# AD9361_EXT.net
KiCad netlist of a schematic drawn in Altium Designer
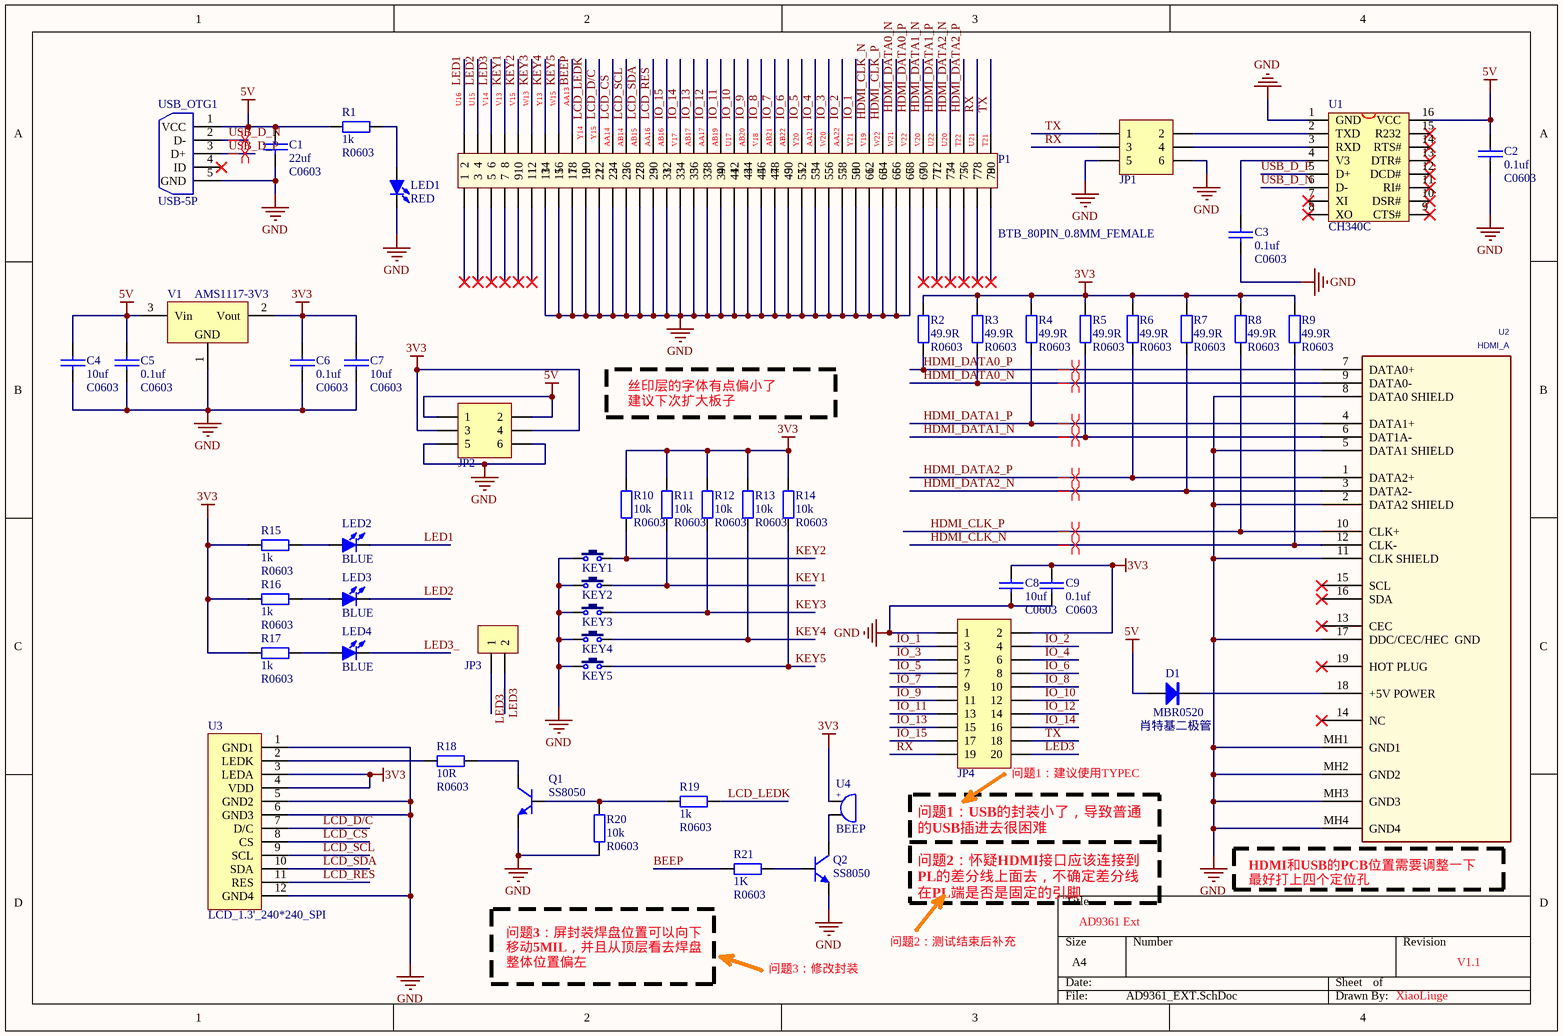
[diagram p0: AD9361_EXT.SchDoc]

(export (version "E")
  (design (tool "Eeschema 10.0.6"))
  (components
    (comp (ref "C1")
      (value "22uf")
      (footprint "C0603")
      (description "0603无极性贴片电容")
      (libsource (lib "电容") (part "CAP_0603"))
    )
    (comp (ref "C2")
      (value "0.1uf")
      (footprint "C0603")
      (description "0603无极性贴片电容")
      (libsource (lib "电容") (part "CAP_0603"))
    )
    (comp (ref "C3")
      (value "0.1uf")
      (footprint "C0603")
      (description "0603无极性贴片电容")
      (libsource (lib "电容") (part "CAP_0603"))
    )
    (comp (ref "C4")
      (value "10uf")
      (footprint "C0603")
      (description "0603无极性贴片电容")
      (libsource (lib "电容") (part "CAP_0603"))
    )
    (comp (ref "C5")
      (value "0.1uf")
      (footprint "C0603")
      (description "0603无极性贴片电容")
      (libsource (lib "电容") (part "CAP_0603"))
    )
    (comp (ref "C6")
      (value "0.1uf")
      (footprint "C0603")
      (description "0603无极性贴片电容")
      (libsource (lib "电容") (part "CAP_0603"))
    )
    (comp (ref "C7")
      (value "10uf")
      (footprint "C0603")
      (description "0603无极性贴片电容")
      (libsource (lib "电容") (part "CAP_0603"))
    )
    (comp (ref "C8")
      (value "10uf")
      (footprint "C0603")
      (description "0603无极性贴片电容")
      (libsource (lib "电容") (part "CAP_0603"))
    )
    (comp (ref "C9")
      (value "0.1uf")
      (footprint "C0603")
      (description "0603无极性贴片电容")
      (libsource (lib "电容") (part "CAP_0603"))
    )
    (comp (ref "D1")
      (value "MBR0520")
      (footprint "SOD-323")
      (description "肖特基二极管")
      (fields (field (name "BOM蜜称") "肖特基二极管"))
      (libsource (lib "二极管") (part "SS14"))
    )
    (comp (ref "JP1")
      (value "Header3X2")
      (footprint "HDR2.54-LI-2x3P")
      (description "3*2P接插件")
      (libsource (lib "排针") (part "Header 3X2"))
    )
    (comp (ref "JP2")
      (value "Header3X2")
      (footprint "HDR2.54-LI-2x3P")
      (description "3*2P接插件")
      (libsource (lib "排针") (part "Header 3X2"))
    )
    (comp (ref "JP3")
      (value "HDR-1X2")
      (footprint "HDR2.54-LI-2P")
      (description "2P接插件")
      (libsource (lib "排针") (part "Header 2"))
    )
    (comp (ref "JP4")
      (value "Header 2X10")
      (footprint "HDR2.54-LI-2x10P")
      (description "10*2P接插件")
      (libsource (lib "排针") (part "Header 10X2"))
    )
    (comp (ref "KEY1")
      (value "KEY")
      (footprint "TSW SMD-6*6*6")
      (description "按键")
      (libsource (lib "小器件") (part "KEY"))
    )
    (comp (ref "KEY2")
      (value "KEY")
      (footprint "TSW SMD-6*6*6")
      (description "按键")
      (libsource (lib "小器件") (part "KEY"))
    )
    (comp (ref "KEY3")
      (value "KEY")
      (footprint "TSW SMD-6*6*6")
      (description "按键")
      (libsource (lib "小器件") (part "KEY"))
    )
    (comp (ref "KEY4")
      (value "KEY")
      (footprint "TSW SMD-6*6*6")
      (description "按键")
      (libsource (lib "小器件") (part "KEY"))
    )
    (comp (ref "KEY5")
      (value "KEY")
      (footprint "TSW SMD-6*6*6")
      (description "按键")
      (libsource (lib "小器件") (part "KEY"))
    )
    (comp (ref "LED1")
      (value "RED")
      (footprint "LED 0603R")
      (description "贴片LED")
      (libsource (lib "小器件") (part "LED-SMD"))
    )
    (comp (ref "LED2")
      (value "BLUE")
      (footprint "LED 0603B")
      (description "贴片LED")
      (libsource (lib "小器件") (part "LED-SMD"))
    )
    (comp (ref "LED3")
      (value "BLUE")
      (footprint "LED 0603B")
      (description "贴片LED")
      (libsource (lib "小器件") (part "LED-SMD"))
    )
    (comp (ref "LED4")
      (value "BLUE")
      (footprint "LED 0603B")
      (description "贴片LED")
      (libsource (lib "小器件") (part "LED-SMD"))
    )
    (comp (ref "P1")
      (value "BTB_80PIN_0.8MM_FEMALE")
      (footprint "BTB_BOTTOM_80PIN_1.27MM")
      (description "BTB接口0.8MM间距母头")
      (libsource (lib "接口器件") (part "BTB_80PIN_0.8MM_FEMALE"))
    )
    (comp (ref "Q1")
      (value "SS8050")
      (footprint "SOT23-3L")
      (description "高频放大-NPN型")
      (libsource (lib "三极管") (part "8050-SMD"))
    )
    (comp (ref "Q2")
      (value "SS8050")
      (footprint "SOT23-3L")
      (description "高频放大-NPN型")
      (libsource (lib "三极管") (part "8050-SMD"))
    )
    (comp (ref "R1")
      (value "1k")
      (footprint "R0603")
      (description "0603电阻")
      (libsource (lib "电阻") (part "RES_0603"))
    )
    (comp (ref "R2")
      (value "49.9R")
      (footprint "R0603")
      (description "0603电阻")
      (libsource (lib "电阻") (part "RES_0603"))
    )
    (comp (ref "R3")
      (value "49.9R")
      (footprint "R0603")
      (description "0603电阻")
      (libsource (lib "电阻") (part "RES_0603"))
    )
    (comp (ref "R4")
      (value "49.9R")
      (footprint "R0603")
      (description "0603电阻")
      (libsource (lib "电阻") (part "RES_0603"))
    )
    (comp (ref "R5")
      (value "49.9R")
      (footprint "R0603")
      (description "0603电阻")
      (libsource (lib "电阻") (part "RES_0603"))
    )
    (comp (ref "R6")
      (value "49.9R")
      (footprint "R0603")
      (description "0603电阻")
      (libsource (lib "电阻") (part "RES_0603"))
    )
    (comp (ref "R7")
      (value "49.9R")
      (footprint "R0603")
      (description "0603电阻")
      (libsource (lib "电阻") (part "RES_0603"))
    )
    (comp (ref "R8")
      (value "49.9R")
      (footprint "R0603")
      (description "0603电阻")
      (libsource (lib "电阻") (part "RES_0603"))
    )
    (comp (ref "R9")
      (value "49.9R")
      (footprint "R0603")
      (description "0603电阻")
      (libsource (lib "电阻") (part "RES_0603"))
    )
    (comp (ref "R10")
      (value "10k")
      (footprint "R0603")
      (description "0603电阻")
      (libsource (lib "电阻") (part "RES_0603"))
    )
    (comp (ref "R11")
      (value "10k")
      (footprint "R0603")
      (description "0603电阻")
      (libsource (lib "电阻") (part "RES_0603"))
    )
    (comp (ref "R12")
      (value "10k")
      (footprint "R0603")
      (description "0603电阻")
      (libsource (lib "电阻") (part "RES_0603"))
    )
    (comp (ref "R13")
      (value "10k")
      (footprint "R0603")
      (description "0603电阻")
      (libsource (lib "电阻") (part "RES_0603"))
    )
    (comp (ref "R14")
      (value "10k")
      (footprint "R0603")
      (description "0603电阻")
      (libsource (lib "电阻") (part "RES_0603"))
    )
    (comp (ref "R15")
      (value "1k")
      (footprint "R0603")
      (description "0603电阻")
      (libsource (lib "电阻") (part "RES_0603"))
    )
    (comp (ref "R16")
      (value "1k")
      (footprint "R0603")
      (description "0603电阻")
      (libsource (lib "电阻") (part "RES_0603"))
    )
    (comp (ref "R17")
      (value "1k")
      (footprint "R0603")
      (description "0603电阻")
      (libsource (lib "电阻") (part "RES_0603"))
    )
    (comp (ref "R18")
      (value "10R")
      (footprint "R0603")
      (description "0603电阻")
      (libsource (lib "电阻") (part "RES_0603"))
    )
    (comp (ref "R19")
      (value "1k")
      (footprint "R0603")
      (description "0603电阻")
      (libsource (lib "电阻") (part "RES_0603"))
    )
    (comp (ref "R20")
      (value "10k")
      (footprint "R0603")
      (description "0603电阻")
      (libsource (lib "电阻") (part "RES_0603"))
    )
    (comp (ref "R21")
      (value "1K")
      (footprint "R0603")
      (description "0603电阻")
      (libsource (lib "电阻") (part "RES_0603"))
    )
    (comp (ref "U1")
      (value "CH340C")
      (footprint "SOP16_N")
      (description "USB2UART")
      (libsource (lib "数字芯片") (part "CH340C"))
    )
    (comp (ref "U2")
      (value "HDMI_A")
      (footprint "HDMI")
      (description "HDMI_A接口")
      (libsource (lib "接口器件") (part "HDMI_A"))
    )
    (comp (ref "U3")
      (value "LCD_1.3'_240*240_SPI")
      (footprint "TFT_1.3'_SPI_RGB_240*240")
      (description "1.3‘_SPI_中景圆屏幕")
      (libsource (lib "屏幕") (part "LCD_1.3'_240*240_SPI"))
    )
    (comp (ref "U4")
      (value "BEEP")
      (footprint "BEEP 5x9x5.5")
      (description "蜂鸣器")
      (libsource (lib "小器件") (part "BEEP"))
    )
    (comp (ref "USB_OTG1")
      (value "USB-5P")
      (footprint "USB-MICRO_A")
      (description "微型USB母座")
      (libsource (lib "接口器件") (part "Micro_USB"))
    )
    (comp (ref "V1")
      (value "AMS1117-3V3")
      (footprint "SOT223_L")
      (description "三端稳压芯片")
      (libsource (lib "模拟芯片") (part "AMS1117"))
    )
  )
  (nets
    (net (code "1") (name "/BEEP") (class "Default")
      (node (ref "P1") (pin "18") (pinfunction "18_18") (pintype "passive"))
      (node (ref "R21") (pin "1") (pinfunction "1_1") (pintype "passive"))
    )
    (net (code "2") (name "/HDMI_CLK_N") (class "Default")
      (node (ref "P1") (pin "62") (pinfunction "62_62") (pintype "passive"))
      (node (ref "R9") (pin "1") (pinfunction "1_1") (pintype "passive"))
      (node (ref "U2") (pin "12") (pinfunction "CLK-_12") (pintype "passive"))
    )
    (net (code "3") (name "/HDMI_CLK_P") (class "Default")
      (node (ref "P1") (pin "64") (pinfunction "64_64") (pintype "passive"))
      (node (ref "R8") (pin "1") (pinfunction "1_1") (pintype "passive"))
      (node (ref "U2") (pin "10") (pinfunction "CLK+_10") (pintype "passive"))
    )
    (net (code "4") (name "/HDMI_DATA0_N") (class "Default")
      (node (ref "P1") (pin "66") (pinfunction "66_66") (pintype "passive"))
      (node (ref "R3") (pin "1") (pinfunction "1_1") (pintype "passive"))
      (node (ref "U2") (pin "9") (pinfunction "DATA0-_9") (pintype "passive"))
    )
    (net (code "5") (name "/HDMI_DATA0_P") (class "Default")
      (node (ref "P1") (pin "68") (pinfunction "68_68") (pintype "passive"))
      (node (ref "R2") (pin "1") (pinfunction "1_1") (pintype "passive"))
      (node (ref "U2") (pin "7") (pinfunction "DATA0+_7") (pintype "passive"))
    )
    (net (code "6") (name "/HDMI_DATA1_N") (class "Default")
      (node (ref "P1") (pin "70") (pinfunction "70_70") (pintype "passive"))
      (node (ref "R5") (pin "1") (pinfunction "1_1") (pintype "passive"))
      (node (ref "U2") (pin "6") (pinfunction "DAT1A-_6") (pintype "passive"))
    )
    (net (code "7") (name "/HDMI_DATA1_P") (class "Default")
      (node (ref "P1") (pin "72") (pinfunction "72_72") (pintype "passive"))
      (node (ref "R4") (pin "1") (pinfunction "1_1") (pintype "passive"))
      (node (ref "U2") (pin "4") (pinfunction "DATA1+_4") (pintype "passive"))
    )
    (net (code "8") (name "/HDMI_DATA2_N") (class "Default")
      (node (ref "P1") (pin "74") (pinfunction "74_74") (pintype "passive"))
      (node (ref "R7") (pin "1") (pinfunction "1_1") (pintype "passive"))
      (node (ref "U2") (pin "3") (pinfunction "DATA2-_3") (pintype "passive"))
    )
    (net (code "9") (name "/HDMI_DATA2_P") (class "Default")
      (node (ref "P1") (pin "76") (pinfunction "76_76") (pintype "passive"))
      (node (ref "R6") (pin "1") (pinfunction "1_1") (pintype "passive"))
      (node (ref "U2") (pin "1") (pinfunction "DATA2+_1") (pintype "passive"))
    )
    (net (code "10") (name "/IO_1") (class "Default")
      (node (ref "JP4") (pin "3") (pinfunction "3_3") (pintype "passive"))
      (node (ref "P1") (pin "60") (pinfunction "60_60") (pintype "passive"))
    )
    (net (code "11") (name "/IO_2") (class "Default")
      (node (ref "JP4") (pin "4") (pinfunction "4_4") (pintype "passive"))
      (node (ref "P1") (pin "58") (pinfunction "58_58") (pintype "passive"))
    )
    (net (code "12") (name "/IO_3") (class "Default")
      (node (ref "JP4") (pin "5") (pinfunction "5_5") (pintype "passive"))
      (node (ref "P1") (pin "56") (pinfunction "56_56") (pintype "passive"))
    )
    (net (code "13") (name "/IO_4") (class "Default")
      (node (ref "JP4") (pin "6") (pinfunction "6_6") (pintype "passive"))
      (node (ref "P1") (pin "54") (pinfunction "54_54") (pintype "passive"))
    )
    (net (code "14") (name "/IO_5") (class "Default")
      (node (ref "JP4") (pin "7") (pinfunction "7_7") (pintype "passive"))
      (node (ref "P1") (pin "52") (pinfunction "52_52") (pintype "passive"))
    )
    (net (code "15") (name "/IO_6") (class "Default")
      (node (ref "JP4") (pin "8") (pinfunction "8_8") (pintype "passive"))
      (node (ref "P1") (pin "50") (pinfunction "50_50") (pintype "passive"))
    )
    (net (code "16") (name "/IO_7") (class "Default")
      (node (ref "JP4") (pin "9") (pinfunction "9_9") (pintype "passive"))
      (node (ref "P1") (pin "48") (pinfunction "48_48") (pintype "passive"))
    )
    (net (code "17") (name "/IO_8") (class "Default")
      (node (ref "JP4") (pin "10") (pinfunction "10_10") (pintype "passive"))
      (node (ref "P1") (pin "46") (pinfunction "46_46") (pintype "passive"))
    )
    (net (code "18") (name "/IO_9") (class "Default")
      (node (ref "JP4") (pin "11") (pinfunction "11_11") (pintype "passive"))
      (node (ref "P1") (pin "44") (pinfunction "44_44") (pintype "passive"))
    )
    (net (code "19") (name "/IO_10") (class "Default")
      (node (ref "JP4") (pin "12") (pinfunction "12_12") (pintype "passive"))
      (node (ref "P1") (pin "42") (pinfunction "42_42") (pintype "passive"))
    )
    (net (code "20") (name "/IO_11") (class "Default")
      (node (ref "JP4") (pin "13") (pinfunction "13_13") (pintype "passive"))
      (node (ref "P1") (pin "40") (pinfunction "40_40") (pintype "passive"))
    )
    (net (code "21") (name "/IO_12") (class "Default")
      (node (ref "JP4") (pin "14") (pinfunction "14_14") (pintype "passive"))
      (node (ref "P1") (pin "38") (pinfunction "38_38") (pintype "passive"))
    )
    (net (code "22") (name "/IO_13") (class "Default")
      (node (ref "JP4") (pin "15") (pinfunction "15_15") (pintype "passive"))
      (node (ref "P1") (pin "36") (pinfunction "36_36") (pintype "passive"))
    )
    (net (code "23") (name "/IO_14") (class "Default")
      (node (ref "JP4") (pin "16") (pinfunction "16_16") (pintype "passive"))
      (node (ref "P1") (pin "34") (pinfunction "34_34") (pintype "passive"))
    )
    (net (code "24") (name "/IO_15") (class "Default")
      (node (ref "JP4") (pin "17") (pinfunction "17_17") (pintype "passive"))
      (node (ref "P1") (pin "32") (pinfunction "32_32") (pintype "passive"))
    )
    (net (code "25") (name "/KEY1") (class "Default")
      (node (ref "KEY2") (pin "2") (pinfunction "2_2") (pintype "passive"))
      (node (ref "P1") (pin "8") (pinfunction "8_8") (pintype "passive"))
      (node (ref "R11") (pin "1") (pinfunction "1_1") (pintype "passive"))
    )
    (net (code "26") (name "/KEY2") (class "Default")
      (node (ref "KEY1") (pin "2") (pinfunction "2_2") (pintype "passive"))
      (node (ref "P1") (pin "10") (pinfunction "10_10") (pintype "passive"))
      (node (ref "R10") (pin "1") (pinfunction "1_1") (pintype "passive"))
    )
    (net (code "27") (name "/KEY3") (class "Default")
      (node (ref "KEY3") (pin "2") (pinfunction "2_2") (pintype "passive"))
      (node (ref "P1") (pin "12") (pinfunction "12_12") (pintype "passive"))
      (node (ref "R12") (pin "1") (pinfunction "1_1") (pintype "passive"))
    )
    (net (code "28") (name "/KEY4") (class "Default")
      (node (ref "KEY4") (pin "2") (pinfunction "2_2") (pintype "passive"))
      (node (ref "P1") (pin "14") (pinfunction "14_14") (pintype "passive"))
      (node (ref "R13") (pin "1") (pinfunction "1_1") (pintype "passive"))
    )
    (net (code "29") (name "/KEY5") (class "Default")
      (node (ref "KEY5") (pin "2") (pinfunction "2_2") (pintype "passive"))
      (node (ref "P1") (pin "16") (pinfunction "16_16") (pintype "passive"))
      (node (ref "R14") (pin "1") (pinfunction "1_1") (pintype "passive"))
    )
    (net (code "30") (name "/LCD_CS") (class "Default")
      (node (ref "P1") (pin "24") (pinfunction "24_24") (pintype "passive"))
      (node (ref "U3") (pin "8") (pinfunction "CS_8") (pintype "passive"))
    )
    (net (code "31") (name "/LCD_D{slash}C") (class "Default")
      (node (ref "P1") (pin "22") (pinfunction "22_22") (pintype "passive"))
      (node (ref "U3") (pin "7") (pinfunction "D/C_7") (pintype "passive"))
    )
    (net (code "32") (name "/LCD_LEDK") (class "Default")
      (node (ref "P1") (pin "20") (pinfunction "20_20") (pintype "passive"))
      (node (ref "R19") (pin "2") (pinfunction "2_2") (pintype "passive"))
    )
    (net (code "33") (name "/LCD_RES") (class "Default")
      (node (ref "P1") (pin "30") (pinfunction "30_30") (pintype "passive"))
      (node (ref "U3") (pin "11") (pinfunction "RES_11") (pintype "passive"))
    )
    (net (code "34") (name "/LCD_SCL") (class "Default")
      (node (ref "P1") (pin "26") (pinfunction "26_26") (pintype "passive"))
      (node (ref "U3") (pin "9") (pinfunction "SCL_9") (pintype "passive"))
    )
    (net (code "35") (name "/LCD_SDA") (class "Default")
      (node (ref "P1") (pin "28") (pinfunction "28_28") (pintype "passive"))
      (node (ref "U3") (pin "10") (pinfunction "SDA_10") (pintype "passive"))
    )
    (net (code "36") (name "/LED1") (class "Default")
      (node (ref "LED2") (pin "2") (pinfunction "K_2") (pintype "passive"))
      (node (ref "P1") (pin "2") (pinfunction "2_2") (pintype "passive"))
    )
    (net (code "37") (name "/LED2") (class "Default")
      (node (ref "LED3") (pin "2") (pinfunction "K_2") (pintype "passive"))
      (node (ref "P1") (pin "4") (pinfunction "4_4") (pintype "passive"))
    )
    (net (code "38") (name "/LED3") (class "Default")
      (node (ref "JP3") (pin "2") (pinfunction "2_2") (pintype "passive"))
      (node (ref "JP4") (pin "20") (pinfunction "20_20") (pintype "passive"))
      (node (ref "P1") (pin "6") (pinfunction "6_6") (pintype "passive"))
    )
    (net (code "39") (name "/LED3_") (class "Default")
      (node (ref "JP3") (pin "1") (pinfunction "1_1") (pintype "passive"))
      (node (ref "LED4") (pin "2") (pinfunction "K_2") (pintype "passive"))
    )
    (net (code "40") (name "/RX") (class "Default")
      (node (ref "JP1") (pin "3") (pinfunction "3_3") (pintype "passive"))
      (node (ref "JP4") (pin "19") (pinfunction "19_19") (pintype "passive"))
      (node (ref "P1") (pin "78") (pinfunction "78_78") (pintype "passive"))
    )
    (net (code "41") (name "/TX") (class "Default")
      (node (ref "JP1") (pin "1") (pinfunction "1_1") (pintype "passive"))
      (node (ref "JP4") (pin "18") (pinfunction "18_18") (pintype "passive"))
      (node (ref "P1") (pin "80") (pinfunction "80_80") (pintype "passive"))
    )
    (net (code "42") (name "/USB_D_N") (class "Default")
      (node (ref "U1") (pin "6") (pinfunction "D-_6") (pintype "passive"))
      (node (ref "USB_OTG1") (pin "2") (pinfunction "D-_2") (pintype "passive"))
    )
    (net (code "43") (name "/USB_D_P") (class "Default")
      (node (ref "U1") (pin "5") (pinfunction "D+_5") (pintype "passive"))
      (node (ref "USB_OTG1") (pin "3") (pinfunction "D+_3") (pintype "passive"))
    )
    (net (code "44") (name "3V3") (class "Default")
      (node (ref "C6") (pin "1") (pinfunction "1_1") (pintype "passive"))
      (node (ref "C7") (pin "1") (pinfunction "1_1") (pintype "passive"))
      (node (ref "C8") (pin "1") (pinfunction "1_1") (pintype "passive"))
      (node (ref "C9") (pin "1") (pinfunction "1_1") (pintype "passive"))
      (node (ref "JP2") (pin "3") (pinfunction "3_3") (pintype "passive"))
      (node (ref "JP2") (pin "4") (pinfunction "4_4") (pintype "passive"))
      (node (ref "JP4") (pin "2") (pinfunction "2_2") (pintype "passive"))
      (node (ref "R10") (pin "2") (pinfunction "2_2") (pintype "passive"))
      (node (ref "R11") (pin "2") (pinfunction "2_2") (pintype "passive"))
      (node (ref "R12") (pin "2") (pinfunction "2_2") (pintype "passive"))
      (node (ref "R13") (pin "2") (pinfunction "2_2") (pintype "passive"))
      (node (ref "R14") (pin "2") (pinfunction "2_2") (pintype "passive"))
      (node (ref "R15") (pin "1") (pinfunction "1_1") (pintype "passive"))
      (node (ref "R16") (pin "1") (pinfunction "1_1") (pintype "passive"))
      (node (ref "R17") (pin "1") (pinfunction "1_1") (pintype "passive"))
      (node (ref "R2") (pin "2") (pinfunction "2_2") (pintype "passive"))
      (node (ref "R3") (pin "2") (pinfunction "2_2") (pintype "passive"))
      (node (ref "R4") (pin "2") (pinfunction "2_2") (pintype "passive"))
      (node (ref "R5") (pin "2") (pinfunction "2_2") (pintype "passive"))
      (node (ref "R6") (pin "2") (pinfunction "2_2") (pintype "passive"))
      (node (ref "R7") (pin "2") (pinfunction "2_2") (pintype "passive"))
      (node (ref "R8") (pin "2") (pinfunction "2_2") (pintype "passive"))
      (node (ref "R9") (pin "2") (pinfunction "2_2") (pintype "passive"))
      (node (ref "U3") (pin "3") (pinfunction "LEDA_3") (pintype "passive"))
      (node (ref "U3") (pin "4") (pinfunction "VDD_4") (pintype "passive"))
      (node (ref "U4") (pin "1") (pinfunction "1_1") (pintype "passive"))
      (node (ref "V1") (pin "2") (pinfunction "Vout_2") (pintype "passive"))
    )
    (net (code "45") (name "5V") (class "Default")
      (node (ref "C1") (pin "1") (pinfunction "1_1") (pintype "passive"))
      (node (ref "C2") (pin "1") (pinfunction "1_1") (pintype "passive"))
      (node (ref "C4") (pin "1") (pinfunction "1_1") (pintype "passive"))
      (node (ref "C5") (pin "1") (pinfunction "1_1") (pintype "passive"))
      (node (ref "D1") (pin "1") (pinfunction "A_1") (pintype "passive"))
      (node (ref "JP2") (pin "1") (pinfunction "1_1") (pintype "passive"))
      (node (ref "JP2") (pin "2") (pinfunction "2_2") (pintype "passive"))
      (node (ref "R1") (pin "1") (pinfunction "1_1") (pintype "passive"))
      (node (ref "U1") (pin "16") (pinfunction "VCC_16") (pintype "passive"))
      (node (ref "USB_OTG1") (pin "1") (pinfunction "VCC_1") (pintype "passive"))
      (node (ref "V1") (pin "3") (pinfunction "Vin_3") (pintype "passive"))
    )
    (net (code "46") (name "GND") (class "Default")
      (node (ref "C1") (pin "2") (pinfunction "2_2") (pintype "passive"))
      (node (ref "C2") (pin "2") (pinfunction "2_2") (pintype "passive"))
      (node (ref "C3") (pin "2") (pinfunction "2_2") (pintype "passive"))
      (node (ref "C4") (pin "2") (pinfunction "2_2") (pintype "passive"))
      (node (ref "C5") (pin "2") (pinfunction "2_2") (pintype "passive"))
      (node (ref "C6") (pin "2") (pinfunction "2_2") (pintype "passive"))
      (node (ref "C7") (pin "2") (pinfunction "2_2") (pintype "passive"))
      (node (ref "C8") (pin "2") (pinfunction "2_2") (pintype "passive"))
      (node (ref "C9") (pin "2") (pinfunction "2_2") (pintype "passive"))
      (node (ref "JP1") (pin "5") (pinfunction "5_5") (pintype "passive"))
      (node (ref "JP1") (pin "6") (pinfunction "6_6") (pintype "passive"))
      (node (ref "JP2") (pin "5") (pinfunction "5_5") (pintype "passive"))
      (node (ref "JP2") (pin "6") (pinfunction "6_6") (pintype "passive"))
      (node (ref "JP4") (pin "1") (pinfunction "1_1") (pintype "passive"))
      (node (ref "KEY1") (pin "1") (pinfunction "1_1") (pintype "passive"))
      (node (ref "KEY2") (pin "1") (pinfunction "1_1") (pintype "passive"))
      (node (ref "KEY3") (pin "1") (pinfunction "1_1") (pintype "passive"))
      (node (ref "KEY4") (pin "1") (pinfunction "1_1") (pintype "passive"))
      (node (ref "KEY5") (pin "1") (pinfunction "1_1") (pintype "passive"))
      (node (ref "LED1") (pin "2") (pinfunction "K_2") (pintype "passive"))
      (node (ref "P1") (pin "13") (pinfunction "13_13") (pintype "passive"))
      (node (ref "P1") (pin "15") (pinfunction "15_15") (pintype "passive"))
      (node (ref "P1") (pin "17") (pinfunction "17_17") (pintype "passive"))
      (node (ref "P1") (pin "19") (pinfunction "19_19") (pintype "passive"))
      (node (ref "P1") (pin "21") (pinfunction "21_21") (pintype "passive"))
      (node (ref "P1") (pin "23") (pinfunction "23_23") (pintype "passive"))
      (node (ref "P1") (pin "25") (pinfunction "25_25") (pintype "passive"))
      (node (ref "P1") (pin "27") (pinfunction "27_27") (pintype "passive"))
      (node (ref "P1") (pin "29") (pinfunction "29_29") (pintype "passive"))
      (node (ref "P1") (pin "31") (pinfunction "31_31") (pintype "passive"))
      (node (ref "P1") (pin "33") (pinfunction "33_33") (pintype "passive"))
      (node (ref "P1") (pin "35") (pinfunction "35_35") (pintype "passive"))
      (node (ref "P1") (pin "37") (pinfunction "37_37") (pintype "passive"))
      (node (ref "P1") (pin "39") (pinfunction "39_39") (pintype "passive"))
      (node (ref "P1") (pin "41") (pinfunction "41_41") (pintype "passive"))
      (node (ref "P1") (pin "43") (pinfunction "43_43") (pintype "passive"))
      (node (ref "P1") (pin "45") (pinfunction "45_45") (pintype "passive"))
      (node (ref "P1") (pin "47") (pinfunction "47_47") (pintype "passive"))
      (node (ref "P1") (pin "49") (pinfunction "49_49") (pintype "passive"))
      (node (ref "P1") (pin "51") (pinfunction "51_51") (pintype "passive"))
      (node (ref "P1") (pin "53") (pinfunction "53_53") (pintype "passive"))
      (node (ref "P1") (pin "55") (pinfunction "55_55") (pintype "passive"))
      (node (ref "P1") (pin "57") (pinfunction "57_57") (pintype "passive"))
      (node (ref "P1") (pin "59") (pinfunction "59_59") (pintype "passive"))
      (node (ref "P1") (pin "61") (pinfunction "61_61") (pintype "passive"))
      (node (ref "P1") (pin "63") (pinfunction "63_63") (pintype "passive"))
      (node (ref "P1") (pin "65") (pinfunction "65_65") (pintype "passive"))
      (node (ref "P1") (pin "67") (pinfunction "67_67") (pintype "passive"))
      (node (ref "Q1") (pin "2") (pinfunction "E_2") (pintype "passive"))
      (node (ref "Q2") (pin "2") (pinfunction "E_2") (pintype "passive"))
      (node (ref "R20") (pin "1") (pinfunction "1_1") (pintype "passive"))
      (node (ref "U1") (pin "1") (pinfunction "GND_1") (pintype "passive"))
      (node (ref "U2") (pin "11") (pinfunction "CLK_SHIELD_11") (pintype "passive"))
      (node (ref "U2") (pin "17") (pinfunction "DDC/CEC/HEC__GND_17") (pintype "passive"))
      (node (ref "U2") (pin "2") (pinfunction "DATA2_SHIELD_2") (pintype "passive"))
      (node (ref "U2") (pin "5") (pinfunction "DATA1_SHIELD_5") (pintype "passive"))
      (node (ref "U2") (pin "8") (pinfunction "DATA0_SHIELD_8") (pintype "passive"))
      (node (ref "U2") (pin "MH1") (pinfunction "GND1_MH1") (pintype "passive"))
      (node (ref "U2") (pin "MH2") (pinfunction "GND2_MH2") (pintype "passive"))
      (node (ref "U2") (pin "MH3") (pinfunction "GND3_MH3") (pintype "passive"))
      (node (ref "U2") (pin "MH4") (pinfunction "GND4_MH4") (pintype "passive"))
      (node (ref "U3") (pin "1") (pinfunction "GND1_1") (pintype "passive"))
      (node (ref "U3") (pin "12") (pinfunction "GND4_12") (pintype "passive"))
      (node (ref "U3") (pin "5") (pinfunction "GND2_5") (pintype "passive"))
      (node (ref "U3") (pin "6") (pinfunction "GND3_6") (pintype "passive"))
      (node (ref "USB_OTG1") (pin "5") (pinfunction "GND_5") (pintype "passive"))
      (node (ref "V1") (pin "1") (pinfunction "GND_1") (pintype "passive"))
    )
    (net (code "47") (name "Net-(D1-K)") (class "Default")
      (node (ref "D1") (pin "2") (pinfunction "K_2") (pintype "passive"))
      (node (ref "U2") (pin "18") (pinfunction "+5V_POWER_18") (pintype "passive"))
    )
    (net (code "48") (name "Net-(LED1-A)") (class "Default")
      (node (ref "LED1") (pin "1") (pinfunction "A_1") (pintype "passive"))
      (node (ref "R1") (pin "2") (pinfunction "2_2") (pintype "passive"))
    )
    (net (code "49") (name "Net-(LED2-A)") (class "Default")
      (node (ref "LED2") (pin "1") (pinfunction "A_1") (pintype "passive"))
      (node (ref "R15") (pin "2") (pinfunction "2_2") (pintype "passive"))
    )
    (net (code "50") (name "Net-(LED3-A)") (class "Default")
      (node (ref "LED3") (pin "1") (pinfunction "A_1") (pintype "passive"))
      (node (ref "R16") (pin "2") (pinfunction "2_2") (pintype "passive"))
    )
    (net (code "51") (name "Net-(LED4-A)") (class "Default")
      (node (ref "LED4") (pin "1") (pinfunction "A_1") (pintype "passive"))
      (node (ref "R17") (pin "2") (pinfunction "2_2") (pintype "passive"))
    )
    (net (code "52") (name "Net-(Q1-B)") (class "Default")
      (node (ref "Q1") (pin "1") (pinfunction "B_1") (pintype "passive"))
      (node (ref "R19") (pin "1") (pinfunction "1_1") (pintype "passive"))
      (node (ref "R20") (pin "2") (pinfunction "2_2") (pintype "passive"))
    )
    (net (code "53") (name "Net-(Q1-C)") (class "Default")
      (node (ref "Q1") (pin "3") (pinfunction "C_3") (pintype "passive"))
      (node (ref "R18") (pin "2") (pinfunction "2_2") (pintype "passive"))
    )
    (net (code "54") (name "Net-(Q2-B)") (class "Default")
      (node (ref "Q2") (pin "1") (pinfunction "B_1") (pintype "passive"))
      (node (ref "R21") (pin "2") (pinfunction "2_2") (pintype "passive"))
    )
    (net (code "55") (name "Net-(Q2-C)") (class "Default")
      (node (ref "Q2") (pin "3") (pinfunction "C_3") (pintype "passive"))
      (node (ref "U4") (pin "2") (pinfunction "2_2") (pintype "passive"))
    )
    (net (code "56") (name "Net-(U1-RXD)") (class "Default")
      (node (ref "JP1") (pin "4") (pinfunction "4_4") (pintype "passive"))
      (node (ref "U1") (pin "3") (pinfunction "RXD_3") (pintype "passive"))
    )
    (net (code "57") (name "Net-(U1-TXD)") (class "Default")
      (node (ref "JP1") (pin "2") (pinfunction "2_2") (pintype "passive"))
      (node (ref "U1") (pin "2") (pinfunction "TXD_2") (pintype "passive"))
    )
    (net (code "58") (name "Net-(U1-V3)") (class "Default")
      (node (ref "C3") (pin "1") (pinfunction "1_1") (pintype "passive"))
      (node (ref "U1") (pin "4") (pinfunction "V3_4") (pintype "passive"))
    )
    (net (code "59") (name "Net-(U3-LEDK)") (class "Default")
      (node (ref "R18") (pin "1") (pinfunction "1_1") (pintype "passive"))
      (node (ref "U3") (pin "2") (pinfunction "LEDK_2") (pintype "passive"))
    )
    (net (code "60") (name "unconnected-(P1-Pad1)") (class "Default")
      (node (ref "P1") (pin "1") (pinfunction "1_1") (pintype "passive+no_connect"))
    )
    (net (code "61") (name "unconnected-(P1-Pad3)") (class "Default")
      (node (ref "P1") (pin "3") (pinfunction "3_3") (pintype "passive+no_connect"))
    )
    (net (code "62") (name "unconnected-(P1-Pad5)") (class "Default")
      (node (ref "P1") (pin "5") (pinfunction "5_5") (pintype "passive+no_connect"))
    )
    (net (code "63") (name "unconnected-(P1-Pad7)") (class "Default")
      (node (ref "P1") (pin "7") (pinfunction "7_7") (pintype "passive+no_connect"))
    )
    (net (code "64") (name "unconnected-(P1-Pad9)") (class "Default")
      (node (ref "P1") (pin "9") (pinfunction "9_9") (pintype "passive+no_connect"))
    )
    (net (code "65") (name "unconnected-(P1-Pad11)") (class "Default")
      (node (ref "P1") (pin "11") (pinfunction "11_11") (pintype "passive+no_connect"))
    )
    (net (code "66") (name "unconnected-(P1-Pad69)") (class "Default")
      (node (ref "P1") (pin "69") (pinfunction "69_69") (pintype "passive+no_connect"))
    )
    (net (code "67") (name "unconnected-(P1-Pad71)") (class "Default")
      (node (ref "P1") (pin "71") (pinfunction "71_71") (pintype "passive+no_connect"))
    )
    (net (code "68") (name "unconnected-(P1-Pad73)") (class "Default")
      (node (ref "P1") (pin "73") (pinfunction "73_73") (pintype "passive+no_connect"))
    )
    (net (code "69") (name "unconnected-(P1-Pad75)") (class "Default")
      (node (ref "P1") (pin "75") (pinfunction "75_75") (pintype "passive+no_connect"))
    )
    (net (code "70") (name "unconnected-(P1-Pad77)") (class "Default")
      (node (ref "P1") (pin "77") (pinfunction "77_77") (pintype "passive+no_connect"))
    )
    (net (code "71") (name "unconnected-(P1-Pad79)") (class "Default")
      (node (ref "P1") (pin "79") (pinfunction "79_79") (pintype "passive+no_connect"))
    )
    (net (code "72") (name "unconnected-(U1-CTS#-Pad9)") (class "Default")
      (node (ref "U1") (pin "9") (pinfunction "CTS#_9") (pintype "passive+no_connect"))
    )
    (net (code "73") (name "unconnected-(U1-DCD#-Pad12)") (class "Default")
      (node (ref "U1") (pin "12") (pinfunction "DCD#_12") (pintype "passive+no_connect"))
    )
    (net (code "74") (name "unconnected-(U1-DSR#-Pad10)") (class "Default")
      (node (ref "U1") (pin "10") (pinfunction "DSR#_10") (pintype "passive+no_connect"))
    )
    (net (code "75") (name "unconnected-(U1-DTR#-Pad13)") (class "Default")
      (node (ref "U1") (pin "13") (pinfunction "DTR#_13") (pintype "passive+no_connect"))
    )
    (net (code "76") (name "unconnected-(U1-R232-Pad15)") (class "Default")
      (node (ref "U1") (pin "15") (pinfunction "R232_15") (pintype "passive+no_connect"))
    )
    (net (code "77") (name "unconnected-(U1-RI#-Pad11)") (class "Default")
      (node (ref "U1") (pin "11") (pinfunction "RI#_11") (pintype "passive+no_connect"))
    )
    (net (code "78") (name "unconnected-(U1-RTS#-Pad14)") (class "Default")
      (node (ref "U1") (pin "14") (pinfunction "RTS#_14") (pintype "passive+no_connect"))
    )
    (net (code "79") (name "unconnected-(U1-XI-Pad7)") (class "Default")
      (node (ref "U1") (pin "7") (pinfunction "XI_7") (pintype "passive+no_connect"))
    )
    (net (code "80") (name "unconnected-(U1-XO-Pad8)") (class "Default")
      (node (ref "U1") (pin "8") (pinfunction "XO_8") (pintype "passive+no_connect"))
    )
    (net (code "81") (name "unconnected-(U2-CEC-Pad13)") (class "Default")
      (node (ref "U2") (pin "13") (pinfunction "CEC_13") (pintype "passive+no_connect"))
    )
    (net (code "82") (name "unconnected-(U2-HOT_PLUG-Pad19)") (class "Default")
      (node (ref "U2") (pin "19") (pinfunction "HOT_PLUG_19") (pintype "passive+no_connect"))
    )
    (net (code "83") (name "unconnected-(U2-NC-Pad14)") (class "Default")
      (node (ref "U2") (pin "14") (pinfunction "NC_14") (pintype "passive+no_connect"))
    )
    (net (code "84") (name "unconnected-(U2-SCL-Pad15)") (class "Default")
      (node (ref "U2") (pin "15") (pinfunction "SCL_15") (pintype "passive+no_connect"))
    )
    (net (code "85") (name "unconnected-(U2-SDA-Pad16)") (class "Default")
      (node (ref "U2") (pin "16") (pinfunction "SDA_16") (pintype "passive+no_connect"))
    )
    (net (code "86") (name "unconnected-(USB_OTG1-ID-Pad4)") (class "Default")
      (node (ref "USB_OTG1") (pin "4") (pinfunction "ID_4") (pintype "passive+no_connect"))
    )
  )
)
